# Pulse_flashlight.net
KiCad netlist of a schematic drawn in Altium Designer
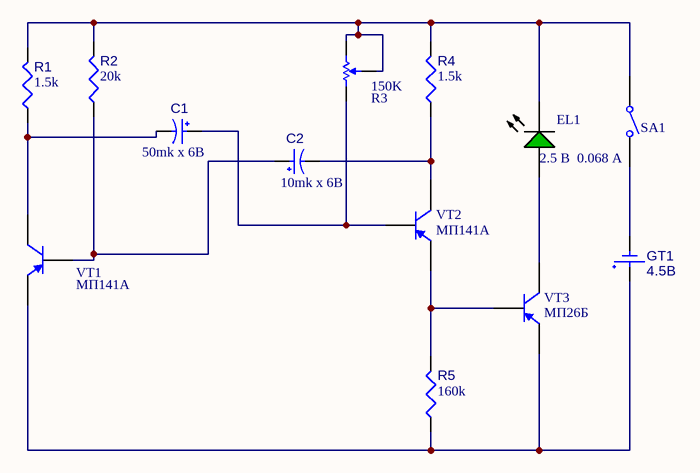
[diagram p0: Pulse flashlight.SchDoc]

(export (version "E")
  (design (tool "Eeschema 10.0.6"))
  (components
    (comp (ref "C1")
      (value "50mk x 6B")
      (footprint "VISH-7343-31_N")
      (fields
        (field (name "TOLERANCE") "10%")
        (field (name "MANUFACTURER") "Vishay Semiconductor")
        (field (name "Comment") "293D107X9010D2TE3")
      )
      (libsource (lib "Yurchenko 20031208") (part "CAP-P-2"))
    )
    (comp (ref "C2")
      (value "10mk x 6B")
      (footprint "VISH-7343-31_N")
      (fields
        (field (name "TOLERANCE") "10%")
        (field (name "MANUFACTURER") "Vishay Semiconductor")
        (field (name "Comment") "293D107X9010D2TE3")
      )
      (libsource (lib "") (part "CAP-P-2_1"))
    )
    (comp (ref "EL1")
      (value "2.5 B  0.068 A")
      (footprint "AVAG-HSMX-C190_V")
      (description "LED Uni-Color Green, 52 mW, 20 mA, -40 to 85 degC, 2-Pin SMD, RoHS, Tape and Reel")
      (fields (field (name "POWER") "52mW") (field (name "MANUFACTURER") "Avago"))
      (libsource (lib "Yurchenko 20031208") (part "LED-GREEN-AK-2"))
    )
    (comp (ref "GT1")
      (value "4.5B")
      (footprint "SEIK-MS621FE-FL11E-2_V")
      (description "MS Lihium Rechargeable Battery, 3 V, -20 to 60 degC, Tray")
      (libsource (lib "Yurchenko 20031208") (part "CMP-00622-2"))
    )
    (comp (ref "R1")
      (value "1.5k")
      (footprint "RESC0805(2012)_L")
      (description "1K 0.125W 5% 0805 (2012 Metric)  SMD")
      (fields (field (name "TOLERANCE") "5%") (field (name "POWER") "125mW"))
      (libsource (lib "Yurchenko 20031208") (part "1KR5J"))
    )
    (comp (ref "R2")
      (value "20k")
      (footprint "RESC0805(2012)_L")
      (description "1K 0.125W 5% 0805 (2012 Metric)  SMD")
      (fields (field (name "TOLERANCE") "5%") (field (name "POWER") "125mW"))
      (libsource (lib "Yurchenko 20031208") (part "1KR5J"))
    )
    (comp (ref "R3")
      (value "150K")
      (footprint "BOUR-TC33X-2_V")
      (description "Trimming Potentiometer, 10000 Ohm, -40 to 100 degC, 3-Pin SMD, RoHS, Tape and Reel")
      (fields (field (name "TOLERANCE") "25%") (field (name "POWER") "100mW"))
      (libsource (lib "Yurchenko 20031208") (part "RES-ADJ-3_A"))
    )
    (comp (ref "R4")
      (value "1.5k")
      (footprint "RESC0805(2012)_L")
      (description "1K 0.125W 5% 0805 (2012 Metric)  SMD")
      (fields (field (name "TOLERANCE") "5%") (field (name "POWER") "125mW"))
      (libsource (lib "Yurchenko 20031208") (part "1KR5J"))
    )
    (comp (ref "R5")
      (value "160k")
      (footprint "RESC0805(2012)_L")
      (description "1K 0.125W 5% 0805 (2012 Metric)  SMD")
      (fields (field (name "TOLERANCE") "5%") (field (name "POWER") "125mW"))
      (libsource (lib "Yurchenko 20031208") (part "1KR5J"))
    )
    (comp (ref "SA1")
      (value "B3U-3000P")
      (footprint "OMRON-B3U-3000P_V")
      (description "Tactile Switch, SPST-NO, 0.05 A, 12 V, -25 to 70 degC, 2-Pin SMD, RoHS, Tape and Reel")
      (fields (field (name "MANUFACTURER") "Omron Electronic Components"))
      (libsource (lib "Yurchenko 20031208") (part "SW-SPST-2_C"))
    )
    (comp (ref "VT1")
      (value "МП141А")
      (footprint "ONSC-SOT-23-3-318-08_V")
      (description "PNP General-Purpose Amplifier, 40 V, 0.2 A, -55 to 150 degC, 3-Pin SOT23, RoHS, Tape and Reel")
      (fields (field (name "POWER") "225mW") (field (name "MANUFACTURER") "ON Semiconductor"))
      (libsource (lib "Yurchenko 20031208") (part "BJT-PNP-BEC-3"))
    )
    (comp (ref "VT2")
      (value "МП141А")
      (footprint "UNIC-TO-92-3")
      (description "Low Voltage High Current Small Signal PNP Transistor, 20 V, 700 mA, 3-Pin TO-92, RoHS")
      (fields (field (name "MANUFACTURER") "Unisonic"))
      (libsource (lib "Yurchenko 20031208") (part "BJT-PNP-EBC-3"))
    )
    (comp (ref "VT3")
      (value "МП26Б")
      (footprint "UNIC-TO-92-3")
      (description "Low Voltage High Current Small Signal PNP Transistor, 20 V, 700 mA, 3-Pin TO-92, RoHS")
      (fields (field (name "MANUFACTURER") "Unisonic"))
      (libsource (lib "Yurchenko 20031208") (part "BJT-PNP-EBC-3"))
    )
  )
  (nets
    (net (code "1") (name "Net-(EL1-A)") (class "Default")
      (node (ref "EL1") (pin "1") (pinfunction "A_1") (pintype "passive"))
      (node (ref "VT3") (pin "3") (pinfunction "C_3") (pintype "passive"))
    )
    (net (code "2") (name "Net-(EL1-K)") (class "Default")
      (node (ref "EL1") (pin "2") (pinfunction "K_2") (pintype "passive"))
      (node (ref "R1") (pin "2") (pinfunction "2_2") (pintype "passive"))
      (node (ref "R2") (pin "2") (pinfunction "2_2") (pintype "passive"))
      (node (ref "R3") (pin "2") (pinfunction "2_2") (pintype "passive"))
      (node (ref "R3") (pin "3") (pinfunction "3_3") (pintype "passive"))
      (node (ref "R4") (pin "2") (pinfunction "2_2") (pintype "passive"))
      (node (ref "SA1") (pin "1") (pinfunction "1_1") (pintype "passive"))
    )
    (net (code "3") (name "Net-(GT1-+)") (class "Default")
      (node (ref "GT1") (pin "1") (pinfunction "+_1") (pintype "passive"))
      (node (ref "R5") (pin "1") (pinfunction "1_1") (pintype "passive"))
      (node (ref "VT1") (pin "2") (pinfunction "E_2") (pintype "passive"))
      (node (ref "VT3") (pin "1") (pinfunction "E_1") (pintype "passive"))
    )
    (net (code "4") (name "Net-(GT1--)") (class "Default")
      (node (ref "GT1") (pin "2") (pinfunction "-_2") (pintype "passive"))
      (node (ref "SA1") (pin "2") (pinfunction "2_2") (pintype "passive"))
    )
    (net (code "5") (name "Net-(VT1-B)") (class "Default")
      (node (ref "C2") (pin "1") (pinfunction "1_1") (pintype "passive"))
      (node (ref "R2") (pin "1") (pinfunction "1_1") (pintype "passive"))
      (node (ref "VT1") (pin "1") (pinfunction "B_1") (pintype "passive"))
    )
    (net (code "6") (name "Net-(VT1-C)") (class "Default")
      (node (ref "C1") (pin "2") (pinfunction "2_2") (pintype "passive"))
      (node (ref "R1") (pin "1") (pinfunction "1_1") (pintype "passive"))
      (node (ref "VT1") (pin "3") (pinfunction "C_3") (pintype "passive"))
    )
    (net (code "7") (name "Net-(VT2-B)") (class "Default")
      (node (ref "C1") (pin "1") (pinfunction "1_1") (pintype "passive"))
      (node (ref "R3") (pin "1") (pinfunction "1_1") (pintype "passive"))
      (node (ref "VT2") (pin "2") (pinfunction "B_2") (pintype "passive"))
    )
    (net (code "8") (name "Net-(VT2-C)") (class "Default")
      (node (ref "C2") (pin "2") (pinfunction "2_2") (pintype "passive"))
      (node (ref "R4") (pin "1") (pinfunction "1_1") (pintype "passive"))
      (node (ref "VT2") (pin "3") (pinfunction "C_3") (pintype "passive"))
    )
    (net (code "9") (name "Net-(VT2-E)") (class "Default")
      (node (ref "R5") (pin "2") (pinfunction "2_2") (pintype "passive"))
      (node (ref "VT2") (pin "1") (pinfunction "E_1") (pintype "passive"))
      (node (ref "VT3") (pin "2") (pinfunction "B_2") (pintype "passive"))
    )
  )
)
